# User_USB.net
KiCad netlist of a schematic drawn in Altium Designer
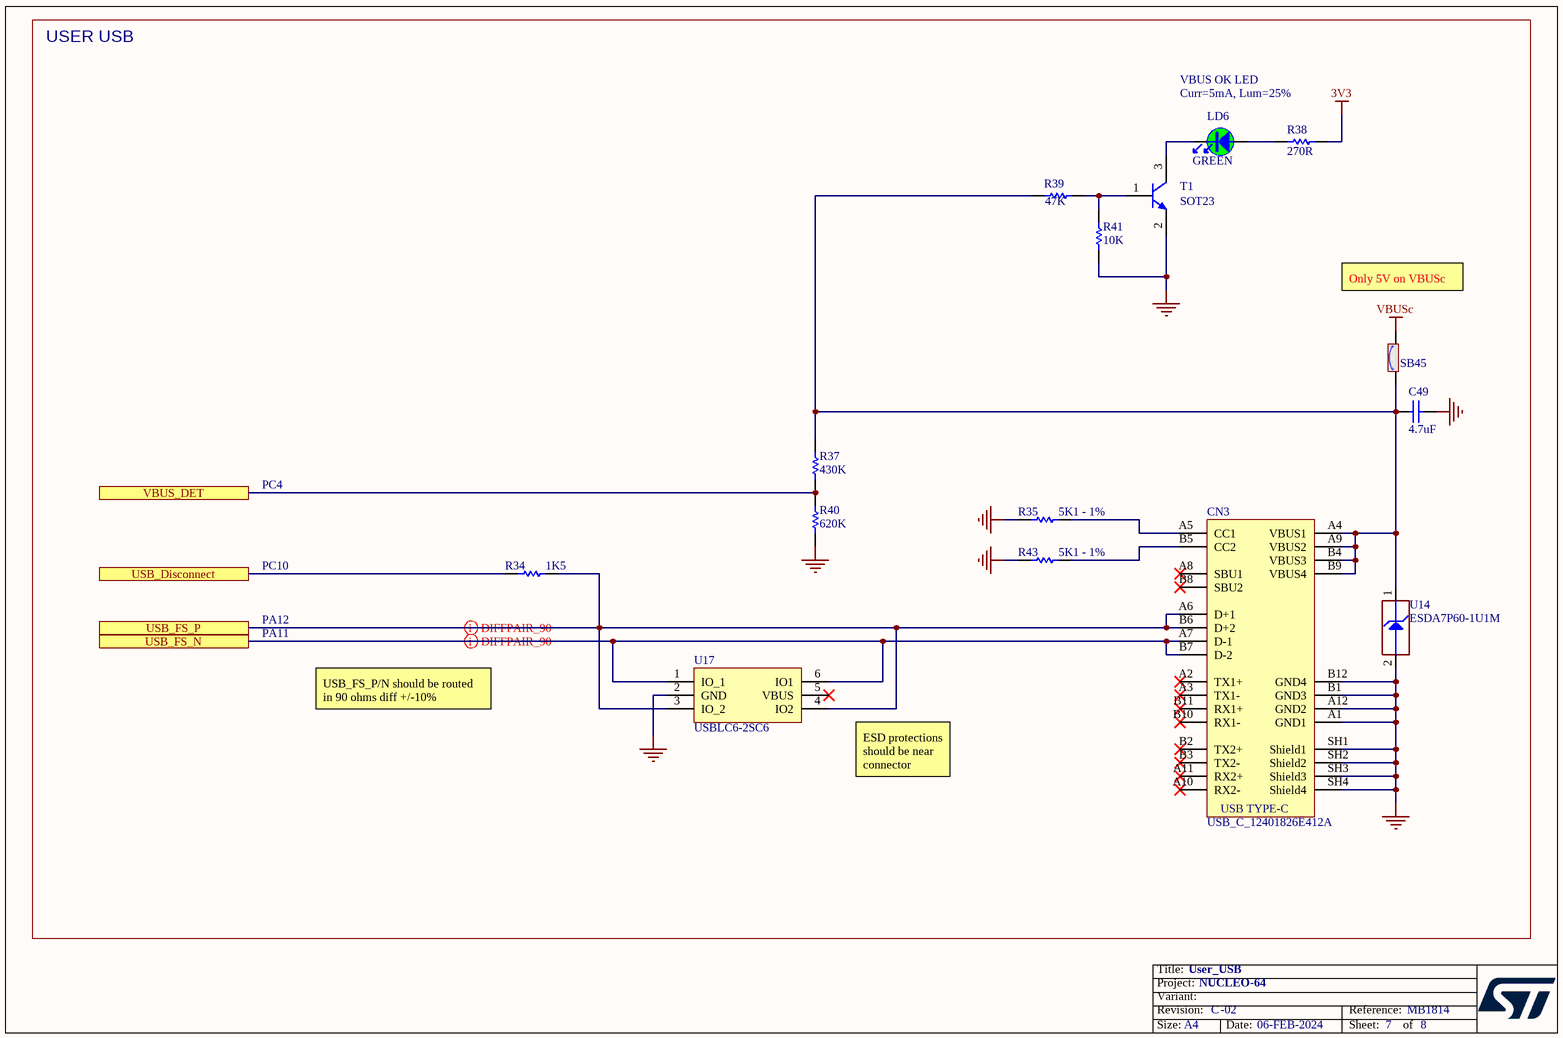
[diagram p0: User_USB.SchDoc]

(export (version "E")
  (design (tool "Eeschema 10.0.6"))
  (components
    (comp (ref "C49")
      (value "4.7uF")
      (footprint "C0603")
      (description "Capacitor, MLCC, 4.7uF, 16V, X5R, 10%, 0603, T=0.8mm")
      (fields
        (field (name "INTERNAL_PART_NUMBER") "MCD-00009")
        (field (name "MANUFACTURER_PART_NUMBER") "CC0603KRX5R7BB475")
        (field (name "PROVIDED_BY") "SUBCO")
      )
      (libsource (lib "MCD_PARTS_database") (part "Capacitor"))
    )
    (comp (ref "CN3")
      (value "USB_C_12401826E412A")
      (footprint "CON_USB-TYPEC_AMPHENOL_12401826E412A")
      (description "USB_TypeC, 24 pins, RA, SMD, T=2.96mm")
      (fields (field (name "INTERNAL_PART_NUMBER") "MCD-03232") (field (name "MANUFACTURER") "AMPHENOL ICC"))
      (libsource (lib "MCD_PARTS_database") (part "USB_TYPE_C_Receptacle"))
    )
    (comp (ref "LD6")
      (value "GREEN")
      (footprint "LED_0603_OSRAM_LG-Q396-PS-35_GREEN_1A2K_H0P4")
      (description "LED Green, 0603 SMD, Forward Voltage Typ=2V, Max=2.5V")
      (fields
        (field (name "INTERNAL_PART_NUMBER") "MCD-00588")
        (field (name "MANUFACTURER_PART_NUMBER") "LG Q396-PS-35")
        (field (name "PROVIDED_BY") "SUBCO")
      )
      (libsource (lib "MCD_PARTS_database") (part "LED_green"))
    )
    (comp (ref "R34")
      (value "1K5")
      (footprint "R0603")
      (description "Resistor, 1K5, 0603, +/-1%, 1/10W")
      (fields (field (name "INTERNAL_PART_NUMBER") "MCD-00217") (field (name "BMS_PART_NUMBER") "9129766"))
      (libsource (lib "MCD_PARTS_database") (part "Resistor"))
    )
    (comp (ref "R35")
      (value "5K1 - 1%")
      (footprint "R0603")
      (description "Resistor, 5K1, 0603, +/-1%, 1/10W")
      (fields (field (name "INTERNAL_PART_NUMBER") "MCD-00334") (field (name "MANUFACTURER") "YAGEO"))
      (libsource (lib "MCD_PARTS_database") (part "Resistor"))
    )
    (comp (ref "R37")
      (value "430K")
      (footprint "R0603")
      (description "Resistor, 430K, 0603, +/-1%, 1/10W")
      (fields (field (name "INTERNAL_PART_NUMBER") "MCD-00480") (field (name "MANUFACTURER") "YAGEO"))
      (libsource (lib "MCD_PARTS_database") (part "Resistor"))
    )
    (comp (ref "R38")
      (value "270R")
      (footprint "R0402")
      (description "Resistor,270R,0402,1%,1/16W")
      (fields
        (field (name "INTERNAL_PART_NUMBER") "MCD-00441")
        (field (name "MANUFACTURER_PART_NUMBER") "RC0402FR-07270RL")
        (field (name "PROVIDED_BY") "SUBCO")
      )
      (libsource (lib "MCD_PARTS_database") (part "Resistor"))
    )
    (comp (ref "R39")
      (value "47K")
      (footprint "R0402")
      (description "Resistor,47K,0402,1%,1/16W")
      (fields
        (field (name "INTERNAL_PART_NUMBER") "MCD-00063")
        (field (name "MANUFACTURER_PART_NUMBER") "RC0402FR-0747KL")
        (field (name "PROVIDED_BY") "SUBCO")
      )
      (libsource (lib "MCD_PARTS_database") (part "Resistor"))
    )
    (comp (ref "R40")
      (value "620K")
      (footprint "R0603")
      (description "Resistor, 620K, 0603, +/-1%, 1/10W")
      (fields (field (name "INTERNAL_PART_NUMBER") "MCD-00506") (field (name "MANUFACTURER") "YAGEO"))
      (libsource (lib "MCD_PARTS_database") (part "Resistor"))
    )
    (comp (ref "R41")
      (value "10K")
      (footprint "R0402")
      (description "Resistor,10K,0402,1%,1/16W")
      (fields
        (field (name "INTERNAL_PART_NUMBER") "MCD-00053")
        (field (name "MANUFACTURER_PART_NUMBER") "RC0402FR-0710KL")
        (field (name "PROVIDED_BY") "SUBCO")
      )
      (libsource (lib "MCD_PARTS_database") (part "Resistor"))
    )
    (comp (ref "R43")
      (value "5K1 - 1%")
      (footprint "R0603")
      (description "Resistor, 5K1, 0603, +/-1%, 1/10W")
      (fields (field (name "INTERNAL_PART_NUMBER") "MCD-00334") (field (name "MANUFACTURER") "YAGEO"))
      (libsource (lib "MCD_PARTS_database") (part "Resistor"))
    )
    (comp (ref "SB45")
      (value "~")
      (footprint "SOLDER-BRIDGE_R0603-0R")
      (description "Solder Bridge ON")
      (fields
        (field (name "INTERNAL_PART_NUMBER") "MCD-00071")
        (field (name "MANUFACTURER_PART_NUMBER") "RC0603JR-070RL")
        (field (name "PROVIDED_BY") "SUBCO")
      )
      (libsource (lib "MCD_PARTS_database") (part "SB_ON"))
    )
    (comp (ref "T1")
      (value "SOT23")
      (footprint "NPN_SOT23")
      (description "NPN Bipolar Transistor")
      (fields
        (field (name "INTERNAL_PART_NUMBER") "MCD-00073")
        (field (name "MANUFACTURER_PART_NUMBER") "BSR14")
        (field (name "PROVIDED_BY") "SUBCO")
      )
      (libsource (lib "MCD_PARTS_database") (part "9013-SOT23"))
    )
    (comp (ref "U14")
      (value "ESDA7P60-1U1M")
      (footprint "ESD_QFN2_1P6X1_P125")
      (description "High power transient voltage suppressor, 7V breakdown")
      (fields (field (name "INTERNAL_PART_NUMBER") "MCD-00251") (field (name "BMS_PART_NUMBER") "9179042"))
      (libsource (lib "MCD_PARTS_database") (part "ESD-TRANSIL"))
    )
    (comp (ref "U17")
      (value "USBLC6-2SC6")
      (footprint "ESD_SOT23-6L")
      (description "Very low capacitance ESD protection")
      (fields
        (field (name "INTERNAL_PART_NUMBER") "MCD-00163")
        (field (name "MANUFACTURER") "STMICROELECTRONICS")
        (field (name "PROVIDED_BY") "SUBCO with ST control")
      )
      (libsource (lib "MCD_PARTS_database") (part "USBLC6-2SC6"))
    )
  )
  (nets
    (net (code "1") (name "/USB_Disconnect") (class "Default")
      (node (ref "R34") (pin "1") (pinfunction "1_1") (pintype "passive"))
    )
    (net (code "2") (name "/USB_FS_N") (class "Default")
      (node (ref "CN3") (pin "A7") (pinfunction "D-1_A7") (pintype "passive"))
      (node (ref "CN3") (pin "B7") (pinfunction "D-2_B7") (pintype "passive"))
      (node (ref "U17") (pin "1") (pinfunction "IO_1_1") (pintype "passive"))
      (node (ref "U17") (pin "6") (pinfunction "IO1_6") (pintype "passive"))
    )
    (net (code "3") (name "/USB_FS_P") (class "Default")
      (node (ref "CN3") (pin "A6") (pinfunction "D+1_A6") (pintype "passive"))
      (node (ref "CN3") (pin "B6") (pinfunction "D+2_B6") (pintype "passive"))
      (node (ref "R34") (pin "2") (pinfunction "2_2") (pintype "passive"))
      (node (ref "U17") (pin "3") (pinfunction "IO_2_3") (pintype "passive"))
      (node (ref "U17") (pin "4") (pinfunction "IO2_4") (pintype "passive"))
    )
    (net (code "4") (name "/VBUS_DET") (class "Default")
      (node (ref "R37") (pin "1") (pinfunction "1_1") (pintype "passive"))
      (node (ref "R40") (pin "2") (pinfunction "2_2") (pintype "passive"))
    )
    (net (code "5") (name "3V3") (class "Default")
      (node (ref "R38") (pin "2") (pinfunction "2_2") (pintype "passive"))
    )
    (net (code "6") (name "GND") (class "Default")
      (node (ref "C49") (pin "1") (pinfunction "1_1") (pintype "passive"))
      (node (ref "CN3") (pin "A1") (pinfunction "GND1_A1") (pintype "passive"))
      (node (ref "CN3") (pin "A12") (pinfunction "GND2_A12") (pintype "passive"))
      (node (ref "CN3") (pin "B1") (pinfunction "GND3_B1") (pintype "passive"))
      (node (ref "CN3") (pin "B12") (pinfunction "GND4_B12") (pintype "passive"))
      (node (ref "CN3") (pin "SH1") (pinfunction "Shield1_SH1") (pintype "passive"))
      (node (ref "CN3") (pin "SH2") (pinfunction "Shield2_SH2") (pintype "passive"))
      (node (ref "CN3") (pin "SH3") (pinfunction "Shield3_SH3") (pintype "passive"))
      (node (ref "CN3") (pin "SH4") (pinfunction "Shield4_SH4") (pintype "passive"))
      (node (ref "R35") (pin "1") (pinfunction "1_1") (pintype "passive"))
      (node (ref "R40") (pin "1") (pinfunction "1_1") (pintype "passive"))
      (node (ref "R41") (pin "1") (pinfunction "1_1") (pintype "passive"))
      (node (ref "R43") (pin "1") (pinfunction "1_1") (pintype "passive"))
      (node (ref "T1") (pin "2") (pinfunction "E_2") (pintype "passive"))
      (node (ref "U14") (pin "2") (pinfunction "GND_2") (pintype "passive"))
      (node (ref "U17") (pin "2") (pinfunction "GND_2") (pintype "passive"))
    )
    (net (code "7") (name "Net-(CN3-CC1)") (class "Default")
      (node (ref "CN3") (pin "A5") (pinfunction "CC1_A5") (pintype "passive"))
      (node (ref "R35") (pin "2") (pinfunction "2_2") (pintype "passive"))
    )
    (net (code "8") (name "Net-(CN3-CC2)") (class "Default")
      (node (ref "CN3") (pin "B5") (pinfunction "CC2_B5") (pintype "passive"))
      (node (ref "R43") (pin "2") (pinfunction "2_2") (pintype "passive"))
    )
    (net (code "9") (name "Net-(CN3-VBUS1)") (class "Default")
      (node (ref "C49") (pin "2") (pinfunction "2_2") (pintype "passive"))
      (node (ref "CN3") (pin "A4") (pinfunction "VBUS1_A4") (pintype "passive"))
      (node (ref "CN3") (pin "A9") (pinfunction "VBUS2_A9") (pintype "passive"))
      (node (ref "CN3") (pin "B4") (pinfunction "VBUS3_B4") (pintype "passive"))
      (node (ref "CN3") (pin "B9") (pinfunction "VBUS4_B9") (pintype "passive"))
      (node (ref "R37") (pin "2") (pinfunction "2_2") (pintype "passive"))
      (node (ref "R39") (pin "1") (pinfunction "1_1") (pintype "passive"))
      (node (ref "SB45") (pin "1") (pinfunction "1_1") (pintype "passive"))
      (node (ref "U14") (pin "1") (pinfunction "IO1_1") (pintype "passive"))
    )
    (net (code "10") (name "Net-(LD6-Pad1)") (class "Default")
      (node (ref "LD6") (pin "1") (pintype "passive"))
      (node (ref "R38") (pin "1") (pinfunction "1_1") (pintype "passive"))
    )
    (net (code "11") (name "Net-(T1-B)") (class "Default")
      (node (ref "R39") (pin "2") (pinfunction "2_2") (pintype "passive"))
      (node (ref "R41") (pin "2") (pinfunction "2_2") (pintype "passive"))
      (node (ref "T1") (pin "1") (pinfunction "B_1") (pintype "passive"))
    )
    (net (code "12") (name "Net-(T1-C)") (class "Default")
      (node (ref "LD6") (pin "2") (pintype "passive"))
      (node (ref "T1") (pin "3") (pinfunction "C_3") (pintype "passive"))
    )
    (net (code "13") (name "VBUSc") (class "Default")
      (node (ref "SB45") (pin "2") (pinfunction "2_2") (pintype "passive"))
    )
    (net (code "14") (name "unconnected-(CN3-RX1+-PadB11)") (class "Default")
      (node (ref "CN3") (pin "B11") (pinfunction "RX1+_B11") (pintype "passive+no_connect"))
    )
    (net (code "15") (name "unconnected-(CN3-RX1--PadB10)") (class "Default")
      (node (ref "CN3") (pin "B10") (pinfunction "RX1-_B10") (pintype "passive+no_connect"))
    )
    (net (code "16") (name "unconnected-(CN3-RX2+-PadA11)") (class "Default")
      (node (ref "CN3") (pin "A11") (pinfunction "RX2+_A11") (pintype "passive+no_connect"))
    )
    (net (code "17") (name "unconnected-(CN3-RX2--PadA10)") (class "Default")
      (node (ref "CN3") (pin "A10") (pinfunction "RX2-_A10") (pintype "passive+no_connect"))
    )
    (net (code "18") (name "unconnected-(CN3-SBU1-PadA8)") (class "Default")
      (node (ref "CN3") (pin "A8") (pinfunction "SBU1_A8") (pintype "passive+no_connect"))
    )
    (net (code "19") (name "unconnected-(CN3-SBU2-PadB8)") (class "Default")
      (node (ref "CN3") (pin "B8") (pinfunction "SBU2_B8") (pintype "passive+no_connect"))
    )
    (net (code "20") (name "unconnected-(CN3-TX1+-PadA2)") (class "Default")
      (node (ref "CN3") (pin "A2") (pinfunction "TX1+_A2") (pintype "passive+no_connect"))
    )
    (net (code "21") (name "unconnected-(CN3-TX1--PadA3)") (class "Default")
      (node (ref "CN3") (pin "A3") (pinfunction "TX1-_A3") (pintype "passive+no_connect"))
    )
    (net (code "22") (name "unconnected-(CN3-TX2+-PadB2)") (class "Default")
      (node (ref "CN3") (pin "B2") (pinfunction "TX2+_B2") (pintype "passive+no_connect"))
    )
    (net (code "23") (name "unconnected-(CN3-TX2--PadB3)") (class "Default")
      (node (ref "CN3") (pin "B3") (pinfunction "TX2-_B3") (pintype "passive+no_connect"))
    )
    (net (code "24") (name "unconnected-(U17-VBUS-Pad5)") (class "Default")
      (node (ref "U17") (pin "5") (pinfunction "VBUS_5") (pintype "passive+no_connect"))
    )
  )
)
